# LED-PCB_DIG0.net
KiCad netlist of a schematic drawn in Altium Designer
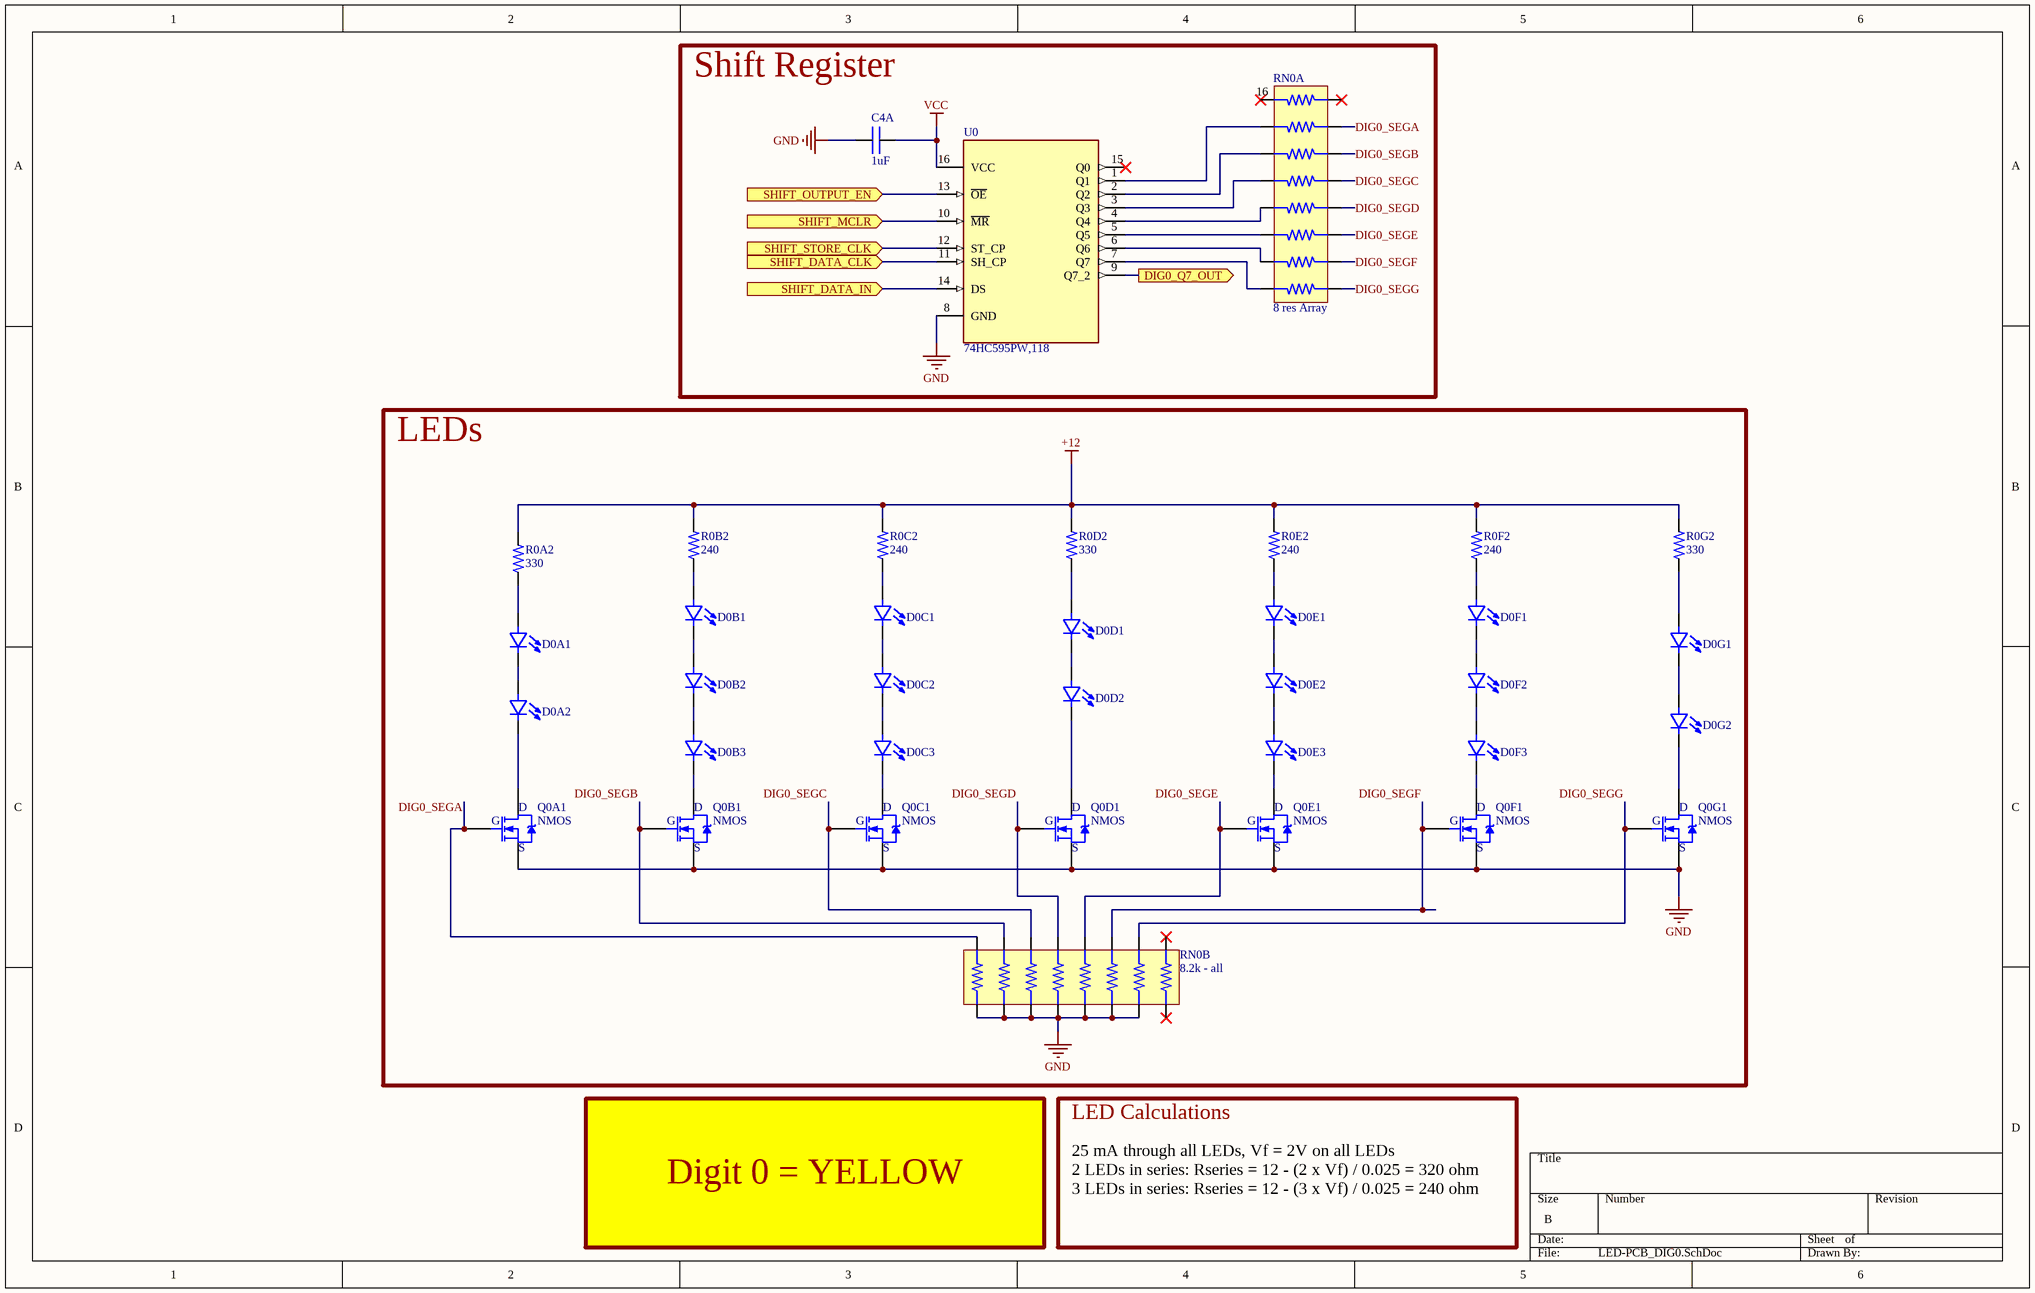
[diagram p0: LED-PCB_DIG0.SchDoc]

(export (version "E")
  (design (tool "Eeschema 10.0.6"))
  (components
    (comp (ref "C4A")
      (value "1uF")
      (footprint "sinking-clock:0402 CAP")
      (description "Capaicitor")
      (fields (field (name "MFR") "Samsung Electro-Mechanics") (field (name "Comment") "CAP"))
      (libsource (lib "sinking-clock") (part "CAP"))
    )
    (comp (ref "D0A1")
      (value "LED - single")
      (footprint "sinking-clock:LED - 0603")
      (fields (field (name "MFR") "Wurth Elektronik"))
      (libsource (lib "sinking-clock") (part "LED - single"))
    )
    (comp (ref "D0A2")
      (value "LED - single")
      (footprint "sinking-clock:LED - 0603")
      (fields (field (name "MFR") "Wurth Elektronik"))
      (libsource (lib "sinking-clock") (part "LED - single"))
    )
    (comp (ref "D0B1")
      (value "LED - single")
      (footprint "sinking-clock:LED - 0603")
      (fields (field (name "MFR") "Wurth Elektronik"))
      (libsource (lib "sinking-clock") (part "LED - single"))
    )
    (comp (ref "D0B2")
      (value "LED - single")
      (footprint "sinking-clock:LED - 0603")
      (fields (field (name "MFR") "Wurth Elektronik"))
      (libsource (lib "sinking-clock") (part "LED - single"))
    )
    (comp (ref "D0B3")
      (value "LED - single")
      (footprint "sinking-clock:LED - 0603")
      (fields (field (name "MFR") "Wurth Elektronik"))
      (libsource (lib "sinking-clock") (part "LED - single"))
    )
    (comp (ref "D0C1")
      (value "LED - single")
      (footprint "sinking-clock:LED - 0603")
      (fields (field (name "MFR") "Wurth Elektronik"))
      (libsource (lib "sinking-clock") (part "LED - single"))
    )
    (comp (ref "D0C2")
      (value "LED - single")
      (footprint "sinking-clock:LED - 0603")
      (fields (field (name "MFR") "Wurth Elektronik"))
      (libsource (lib "sinking-clock") (part "LED - single"))
    )
    (comp (ref "D0C3")
      (value "LED - single")
      (footprint "sinking-clock:LED - 0603")
      (fields (field (name "MFR") "Wurth Elektronik"))
      (libsource (lib "sinking-clock") (part "LED - single"))
    )
    (comp (ref "D0D1")
      (value "LED - single")
      (footprint "sinking-clock:LED - 0603")
      (fields (field (name "MFR") "Wurth Elektronik"))
      (libsource (lib "sinking-clock") (part "LED - single"))
    )
    (comp (ref "D0D2")
      (value "LED - single")
      (footprint "sinking-clock:LED - 0603")
      (fields (field (name "MFR") "Wurth Elektronik"))
      (libsource (lib "sinking-clock") (part "LED - single"))
    )
    (comp (ref "D0E1")
      (value "LED - single")
      (footprint "sinking-clock:LED - 0603")
      (fields (field (name "MFR") "Wurth Elektronik"))
      (libsource (lib "sinking-clock") (part "LED - single"))
    )
    (comp (ref "D0E2")
      (value "LED - single")
      (footprint "sinking-clock:LED - 0603")
      (fields (field (name "MFR") "Wurth Elektronik"))
      (libsource (lib "sinking-clock") (part "LED - single"))
    )
    (comp (ref "D0E3")
      (value "LED - single")
      (footprint "sinking-clock:LED - 0603")
      (fields (field (name "MFR") "Wurth Elektronik"))
      (libsource (lib "sinking-clock") (part "LED - single"))
    )
    (comp (ref "D0F1")
      (value "LED - single")
      (footprint "sinking-clock:LED - 0603")
      (fields (field (name "MFR") "Wurth Elektronik"))
      (libsource (lib "sinking-clock") (part "LED - single"))
    )
    (comp (ref "D0F2")
      (value "LED - single")
      (footprint "sinking-clock:LED - 0603")
      (fields (field (name "MFR") "Wurth Elektronik"))
      (libsource (lib "sinking-clock") (part "LED - single"))
    )
    (comp (ref "D0F3")
      (value "LED - single")
      (footprint "sinking-clock:LED - 0603")
      (fields (field (name "MFR") "Wurth Elektronik"))
      (libsource (lib "sinking-clock") (part "LED - single"))
    )
    (comp (ref "D0G1")
      (value "LED - single")
      (footprint "sinking-clock:LED - 0603")
      (fields (field (name "MFR") "Wurth Elektronik"))
      (libsource (lib "sinking-clock") (part "LED - single"))
    )
    (comp (ref "D0G2")
      (value "LED - single")
      (footprint "sinking-clock:LED - 0603")
      (fields (field (name "MFR") "Wurth Elektronik"))
      (libsource (lib "sinking-clock") (part "LED - single"))
    )
    (comp (ref "Q0A1")
      (value "NMOS")
      (footprint "sinking-clock:SOT-23")
      (description "N-Channel MOSFET")
      (fields (field (name "MFR") "Diodes Incorporated"))
      (libsource (lib "sinking-clock") (part "NMOS"))
    )
    (comp (ref "Q0B1")
      (value "NMOS")
      (footprint "sinking-clock:SOT-23")
      (description "N-Channel MOSFET")
      (fields (field (name "MFR") "Diodes Incorporated"))
      (libsource (lib "sinking-clock") (part "NMOS"))
    )
    (comp (ref "Q0C1")
      (value "NMOS")
      (footprint "sinking-clock:SOT-23")
      (description "N-Channel MOSFET")
      (fields (field (name "MFR") "Diodes Incorporated"))
      (libsource (lib "sinking-clock") (part "NMOS"))
    )
    (comp (ref "Q0D1")
      (value "NMOS")
      (footprint "sinking-clock:SOT-23")
      (description "N-Channel MOSFET")
      (fields (field (name "MFR") "Diodes Incorporated"))
      (libsource (lib "sinking-clock") (part "NMOS"))
    )
    (comp (ref "Q0E1")
      (value "NMOS")
      (footprint "sinking-clock:SOT-23")
      (description "N-Channel MOSFET")
      (fields (field (name "MFR") "Diodes Incorporated"))
      (libsource (lib "sinking-clock") (part "NMOS"))
    )
    (comp (ref "Q0F1")
      (value "NMOS")
      (footprint "sinking-clock:SOT-23")
      (description "N-Channel MOSFET")
      (fields (field (name "MFR") "Diodes Incorporated"))
      (libsource (lib "sinking-clock") (part "NMOS"))
    )
    (comp (ref "Q0G1")
      (value "NMOS")
      (footprint "sinking-clock:SOT-23")
      (description "N-Channel MOSFET")
      (fields (field (name "MFR") "Diodes Incorporated"))
      (libsource (lib "sinking-clock") (part "NMOS"))
    )
    (comp (ref "R0A2")
      (value "330")
      (footprint "sinking-clock:0402 RES")
      (description "Resistor")
      (fields (field (name "MFR") "YAGEO") (field (name "Comment") "RES"))
      (libsource (lib "sinking-clock") (part "RES"))
    )
    (comp (ref "R0B2")
      (value "240")
      (footprint "sinking-clock:0402 RES")
      (description "Resistor")
      (fields (field (name "MFR") "YAGEO") (field (name "Comment") "RES"))
      (libsource (lib "sinking-clock") (part "RES"))
    )
    (comp (ref "R0C2")
      (value "240")
      (footprint "sinking-clock:0402 RES")
      (description "Resistor")
      (fields (field (name "MFR") "YAGEO") (field (name "Comment") "RES"))
      (libsource (lib "sinking-clock") (part "RES"))
    )
    (comp (ref "R0D2")
      (value "330")
      (footprint "sinking-clock:0402 RES")
      (description "Resistor")
      (fields (field (name "MFR") "YAGEO") (field (name "Comment") "RES"))
      (libsource (lib "sinking-clock") (part "RES"))
    )
    (comp (ref "R0E2")
      (value "240")
      (footprint "sinking-clock:0402 RES")
      (description "Resistor")
      (fields (field (name "MFR") "YAGEO") (field (name "Comment") "RES"))
      (libsource (lib "sinking-clock") (part "RES"))
    )
    (comp (ref "R0F2")
      (value "240")
      (footprint "sinking-clock:0402 RES")
      (description "Resistor")
      (fields (field (name "MFR") "YAGEO") (field (name "Comment") "RES"))
      (libsource (lib "sinking-clock") (part "RES"))
    )
    (comp (ref "R0G2")
      (value "330")
      (footprint "sinking-clock:0402 RES")
      (description "Resistor")
      (fields (field (name "MFR") "YAGEO") (field (name "Comment") "RES"))
      (libsource (lib "sinking-clock") (part "RES"))
    )
    (comp (ref "RN0A")
      (value "8 res Array")
      (footprint "sinking-clock:EXB2HV331JV")
      (fields (field (name "MFR") "Panasonic Electronic Components"))
      (libsource (lib "sinking-clock") (part "8 res Array"))
    )
    (comp (ref "RN0B")
      (value "8.2k - all")
      (footprint "sinking-clock:MNR18ERAPJ822")
      (fields (field (name "MFR") "Rohm Semiconductor"))
      (libsource (lib "sinking-clock") (part "MNR18ERAPJ822"))
    )
    (comp (ref "U0")
      (value "74HC595PW,118")
      (footprint "sinking-clock:16-TSSOP")
      (description "Shift Shift Register 1 Element 8 Bit 16-TSSOP")
      (fields (field (name "MFR") "Nexperia USA"))
      (libsource (lib "sinking-clock") (part "74HC595PW,118"))
    )
  )
  (nets
    (net (code "1") (name "+12") (class "Default")
      (node (ref "R0A2") (pin "2") (pinfunction "2_2") (pintype "passive"))
      (node (ref "R0B2") (pin "2") (pinfunction "2_2") (pintype "passive"))
      (node (ref "R0C2") (pin "2") (pinfunction "2_2") (pintype "passive"))
      (node (ref "R0D2") (pin "2") (pinfunction "2_2") (pintype "passive"))
      (node (ref "R0E2") (pin "2") (pinfunction "2_2") (pintype "passive"))
      (node (ref "R0F2") (pin "2") (pinfunction "2_2") (pintype "passive"))
      (node (ref "R0G2") (pin "2") (pinfunction "2_2") (pintype "passive"))
    )
    (net (code "2") (name "/DIG0_Q7_OUT") (class "Default")
      (node (ref "U0") (pin "9") (pinfunction "Q7_2_9") (pintype "output"))
    )
    (net (code "3") (name "/DIG0_SEGA") (class "Default")
      (node (ref "Q0A1") (pin "1") (pinfunction "G_1") (pintype "passive"))
      (node (ref "RN0A") (pin "2") (pinfunction "2_2") (pintype "passive"))
      (node (ref "RN0B") (pin "16") (pinfunction "16_16") (pintype "passive"))
    )
    (net (code "4") (name "/DIG0_SEGB") (class "Default")
      (node (ref "Q0B1") (pin "1") (pinfunction "G_1") (pintype "passive"))
      (node (ref "RN0A") (pin "3") (pinfunction "3_3") (pintype "passive"))
      (node (ref "RN0B") (pin "15") (pinfunction "15_15") (pintype "passive"))
    )
    (net (code "5") (name "/DIG0_SEGC") (class "Default")
      (node (ref "Q0C1") (pin "1") (pinfunction "G_1") (pintype "passive"))
      (node (ref "RN0A") (pin "4") (pinfunction "4_4") (pintype "passive"))
      (node (ref "RN0B") (pin "14") (pinfunction "14_14") (pintype "passive"))
    )
    (net (code "6") (name "/DIG0_SEGD") (class "Default")
      (node (ref "Q0D1") (pin "1") (pinfunction "G_1") (pintype "passive"))
      (node (ref "RN0A") (pin "5") (pinfunction "5_5") (pintype "passive"))
      (node (ref "RN0B") (pin "13") (pinfunction "13_13") (pintype "passive"))
    )
    (net (code "7") (name "/DIG0_SEGE") (class "Default")
      (node (ref "Q0E1") (pin "1") (pinfunction "G_1") (pintype "passive"))
      (node (ref "RN0A") (pin "6") (pinfunction "6_6") (pintype "passive"))
      (node (ref "RN0B") (pin "12") (pinfunction "12_12") (pintype "passive"))
    )
    (net (code "8") (name "/DIG0_SEGF") (class "Default")
      (node (ref "Q0F1") (pin "1") (pinfunction "G_1") (pintype "passive"))
      (node (ref "RN0A") (pin "7") (pinfunction "7_7") (pintype "passive"))
      (node (ref "RN0B") (pin "11") (pinfunction "11_11") (pintype "passive"))
    )
    (net (code "9") (name "/DIG0_SEGG") (class "Default")
      (node (ref "Q0G1") (pin "1") (pinfunction "G_1") (pintype "passive"))
      (node (ref "RN0A") (pin "8") (pinfunction "8_8") (pintype "passive"))
      (node (ref "RN0B") (pin "10") (pinfunction "10_10") (pintype "passive"))
    )
    (net (code "10") (name "/SHIFT_DATA_CLK") (class "Default")
      (node (ref "U0") (pin "11") (pinfunction "SH_CP_11") (pintype "input"))
    )
    (net (code "11") (name "/SHIFT_DATA_IN") (class "Default")
      (node (ref "U0") (pin "14") (pinfunction "DS_14") (pintype "input"))
    )
    (net (code "12") (name "/SHIFT_MCLR") (class "Default")
      (node (ref "U0") (pin "10") (pinfunction "~{MR}_10") (pintype "input"))
    )
    (net (code "13") (name "/SHIFT_OUTPUT_EN") (class "Default")
      (node (ref "U0") (pin "13") (pinfunction "~{OE}_13") (pintype "input"))
    )
    (net (code "14") (name "/SHIFT_STORE_CLK") (class "Default")
      (node (ref "U0") (pin "12") (pinfunction "ST_CP_12") (pintype "input"))
    )
    (net (code "15") (name "GND") (class "Default")
      (node (ref "C4A") (pin "1") (pinfunction "1_1") (pintype "passive"))
      (node (ref "Q0A1") (pin "2") (pinfunction "S_2") (pintype "passive"))
      (node (ref "Q0B1") (pin "2") (pinfunction "S_2") (pintype "passive"))
      (node (ref "Q0C1") (pin "2") (pinfunction "S_2") (pintype "passive"))
      (node (ref "Q0D1") (pin "2") (pinfunction "S_2") (pintype "passive"))
      (node (ref "Q0E1") (pin "2") (pinfunction "S_2") (pintype "passive"))
      (node (ref "Q0F1") (pin "2") (pinfunction "S_2") (pintype "passive"))
      (node (ref "Q0G1") (pin "2") (pinfunction "S_2") (pintype "passive"))
      (node (ref "RN0B") (pin "1") (pinfunction "1_1") (pintype "passive"))
      (node (ref "RN0B") (pin "2") (pinfunction "2_2") (pintype "passive"))
      (node (ref "RN0B") (pin "3") (pinfunction "3_3") (pintype "passive"))
      (node (ref "RN0B") (pin "4") (pinfunction "4_4") (pintype "passive"))
      (node (ref "RN0B") (pin "5") (pinfunction "5_5") (pintype "passive"))
      (node (ref "RN0B") (pin "6") (pinfunction "6_6") (pintype "passive"))
      (node (ref "RN0B") (pin "7") (pinfunction "7_7") (pintype "passive"))
      (node (ref "U0") (pin "8") (pinfunction "GND_8") (pintype "passive"))
    )
    (net (code "16") (name "Net-(D0A1-A)") (class "Default")
      (node (ref "D0A1") (pin "1") (pinfunction "A_1") (pintype "passive"))
      (node (ref "R0A2") (pin "1") (pinfunction "1_1") (pintype "passive"))
    )
    (net (code "17") (name "Net-(D0A1-C)") (class "Default")
      (node (ref "D0A1") (pin "2") (pinfunction "C_2") (pintype "passive"))
      (node (ref "D0A2") (pin "1") (pinfunction "A_1") (pintype "passive"))
    )
    (net (code "18") (name "Net-(D0A2-C)") (class "Default")
      (node (ref "D0A2") (pin "2") (pinfunction "C_2") (pintype "passive"))
      (node (ref "Q0A1") (pin "3") (pinfunction "D_3") (pintype "passive"))
    )
    (net (code "19") (name "Net-(D0B1-A)") (class "Default")
      (node (ref "D0B1") (pin "1") (pinfunction "A_1") (pintype "passive"))
      (node (ref "R0B2") (pin "1") (pinfunction "1_1") (pintype "passive"))
    )
    (net (code "20") (name "Net-(D0B1-C)") (class "Default")
      (node (ref "D0B1") (pin "2") (pinfunction "C_2") (pintype "passive"))
      (node (ref "D0B2") (pin "1") (pinfunction "A_1") (pintype "passive"))
    )
    (net (code "21") (name "Net-(D0B2-C)") (class "Default")
      (node (ref "D0B2") (pin "2") (pinfunction "C_2") (pintype "passive"))
      (node (ref "D0B3") (pin "1") (pinfunction "A_1") (pintype "passive"))
    )
    (net (code "22") (name "Net-(D0B3-C)") (class "Default")
      (node (ref "D0B3") (pin "2") (pinfunction "C_2") (pintype "passive"))
      (node (ref "Q0B1") (pin "3") (pinfunction "D_3") (pintype "passive"))
    )
    (net (code "23") (name "Net-(D0C1-A)") (class "Default")
      (node (ref "D0C1") (pin "1") (pinfunction "A_1") (pintype "passive"))
      (node (ref "R0C2") (pin "1") (pinfunction "1_1") (pintype "passive"))
    )
    (net (code "24") (name "Net-(D0C1-C)") (class "Default")
      (node (ref "D0C1") (pin "2") (pinfunction "C_2") (pintype "passive"))
      (node (ref "D0C2") (pin "1") (pinfunction "A_1") (pintype "passive"))
    )
    (net (code "25") (name "Net-(D0C2-C)") (class "Default")
      (node (ref "D0C2") (pin "2") (pinfunction "C_2") (pintype "passive"))
      (node (ref "D0C3") (pin "1") (pinfunction "A_1") (pintype "passive"))
    )
    (net (code "26") (name "Net-(D0C3-C)") (class "Default")
      (node (ref "D0C3") (pin "2") (pinfunction "C_2") (pintype "passive"))
      (node (ref "Q0C1") (pin "3") (pinfunction "D_3") (pintype "passive"))
    )
    (net (code "27") (name "Net-(D0D1-A)") (class "Default")
      (node (ref "D0D1") (pin "1") (pinfunction "A_1") (pintype "passive"))
      (node (ref "R0D2") (pin "1") (pinfunction "1_1") (pintype "passive"))
    )
    (net (code "28") (name "Net-(D0D1-C)") (class "Default")
      (node (ref "D0D1") (pin "2") (pinfunction "C_2") (pintype "passive"))
      (node (ref "D0D2") (pin "1") (pinfunction "A_1") (pintype "passive"))
    )
    (net (code "29") (name "Net-(D0D2-C)") (class "Default")
      (node (ref "D0D2") (pin "2") (pinfunction "C_2") (pintype "passive"))
      (node (ref "Q0D1") (pin "3") (pinfunction "D_3") (pintype "passive"))
    )
    (net (code "30") (name "Net-(D0E1-A)") (class "Default")
      (node (ref "D0E1") (pin "1") (pinfunction "A_1") (pintype "passive"))
      (node (ref "R0E2") (pin "1") (pinfunction "1_1") (pintype "passive"))
    )
    (net (code "31") (name "Net-(D0E1-C)") (class "Default")
      (node (ref "D0E1") (pin "2") (pinfunction "C_2") (pintype "passive"))
      (node (ref "D0E2") (pin "1") (pinfunction "A_1") (pintype "passive"))
    )
    (net (code "32") (name "Net-(D0E2-C)") (class "Default")
      (node (ref "D0E2") (pin "2") (pinfunction "C_2") (pintype "passive"))
      (node (ref "D0E3") (pin "1") (pinfunction "A_1") (pintype "passive"))
    )
    (net (code "33") (name "Net-(D0E3-C)") (class "Default")
      (node (ref "D0E3") (pin "2") (pinfunction "C_2") (pintype "passive"))
      (node (ref "Q0E1") (pin "3") (pinfunction "D_3") (pintype "passive"))
    )
    (net (code "34") (name "Net-(D0F1-A)") (class "Default")
      (node (ref "D0F1") (pin "1") (pinfunction "A_1") (pintype "passive"))
      (node (ref "R0F2") (pin "1") (pinfunction "1_1") (pintype "passive"))
    )
    (net (code "35") (name "Net-(D0F1-C)") (class "Default")
      (node (ref "D0F1") (pin "2") (pinfunction "C_2") (pintype "passive"))
      (node (ref "D0F2") (pin "1") (pinfunction "A_1") (pintype "passive"))
    )
    (net (code "36") (name "Net-(D0F2-C)") (class "Default")
      (node (ref "D0F2") (pin "2") (pinfunction "C_2") (pintype "passive"))
      (node (ref "D0F3") (pin "1") (pinfunction "A_1") (pintype "passive"))
    )
    (net (code "37") (name "Net-(D0F3-C)") (class "Default")
      (node (ref "D0F3") (pin "2") (pinfunction "C_2") (pintype "passive"))
      (node (ref "Q0F1") (pin "3") (pinfunction "D_3") (pintype "passive"))
    )
    (net (code "38") (name "Net-(D0G1-A)") (class "Default")
      (node (ref "D0G1") (pin "1") (pinfunction "A_1") (pintype "passive"))
      (node (ref "R0G2") (pin "1") (pinfunction "1_1") (pintype "passive"))
    )
    (net (code "39") (name "Net-(D0G1-C)") (class "Default")
      (node (ref "D0G1") (pin "2") (pinfunction "C_2") (pintype "passive"))
      (node (ref "D0G2") (pin "1") (pinfunction "A_1") (pintype "passive"))
    )
    (net (code "40") (name "Net-(D0G2-C)") (class "Default")
      (node (ref "D0G2") (pin "2") (pinfunction "C_2") (pintype "passive"))
      (node (ref "Q0G1") (pin "3") (pinfunction "D_3") (pintype "passive"))
    )
    (net (code "41") (name "Net-(U0-Q1)") (class "Default")
      (node (ref "RN0A") (pin "15") (pinfunction "15_15") (pintype "passive"))
      (node (ref "U0") (pin "1") (pinfunction "Q1_1") (pintype "output"))
    )
    (net (code "42") (name "Net-(U0-Q2)") (class "Default")
      (node (ref "RN0A") (pin "14") (pinfunction "14_14") (pintype "passive"))
      (node (ref "U0") (pin "2") (pinfunction "Q2_2") (pintype "output"))
    )
    (net (code "43") (name "Net-(U0-Q3)") (class "Default")
      (node (ref "RN0A") (pin "13") (pinfunction "13_13") (pintype "passive"))
      (node (ref "U0") (pin "3") (pinfunction "Q3_3") (pintype "output"))
    )
    (net (code "44") (name "Net-(U0-Q4)") (class "Default")
      (node (ref "RN0A") (pin "12") (pinfunction "12_12") (pintype "passive"))
      (node (ref "U0") (pin "4") (pinfunction "Q4_4") (pintype "output"))
    )
    (net (code "45") (name "Net-(U0-Q5)") (class "Default")
      (node (ref "RN0A") (pin "11") (pinfunction "11_11") (pintype "passive"))
      (node (ref "U0") (pin "5") (pinfunction "Q5_5") (pintype "output"))
    )
    (net (code "46") (name "Net-(U0-Q6)") (class "Default")
      (node (ref "RN0A") (pin "10") (pinfunction "10_10") (pintype "passive"))
      (node (ref "U0") (pin "6") (pinfunction "Q6_6") (pintype "output"))
    )
    (net (code "47") (name "Net-(U0-Q7)") (class "Default")
      (node (ref "RN0A") (pin "9") (pinfunction "9_9") (pintype "passive"))
      (node (ref "U0") (pin "7") (pinfunction "Q7_7") (pintype "output"))
    )
    (net (code "48") (name "VCC") (class "Default")
      (node (ref "C4A") (pin "2") (pinfunction "2_2") (pintype "passive"))
      (node (ref "U0") (pin "16") (pinfunction "VCC_16") (pintype "power_in"))
    )
    (net (code "49") (name "unconnected-(RN0A-Pad1)") (class "Default")
      (node (ref "RN0A") (pin "1") (pinfunction "1_1") (pintype "passive+no_connect"))
    )
    (net (code "50") (name "unconnected-(RN0A-Pad16)") (class "Default")
      (node (ref "RN0A") (pin "16") (pinfunction "16_16") (pintype "passive+no_connect"))
    )
    (net (code "51") (name "unconnected-(RN0B-Pad8)") (class "Default")
      (node (ref "RN0B") (pin "8") (pinfunction "8_8") (pintype "passive+no_connect"))
    )
    (net (code "52") (name "unconnected-(RN0B-Pad9)") (class "Default")
      (node (ref "RN0B") (pin "9") (pinfunction "9_9") (pintype "passive+no_connect"))
    )
    (net (code "53") (name "unconnected-(U0-Q0-Pad15)") (class "Default")
      (node (ref "U0") (pin "15") (pinfunction "Q0_15") (pintype "output+no_connect"))
    )
  )
)
